# Boost.net
KiCad netlist of a schematic drawn in Altium Designer
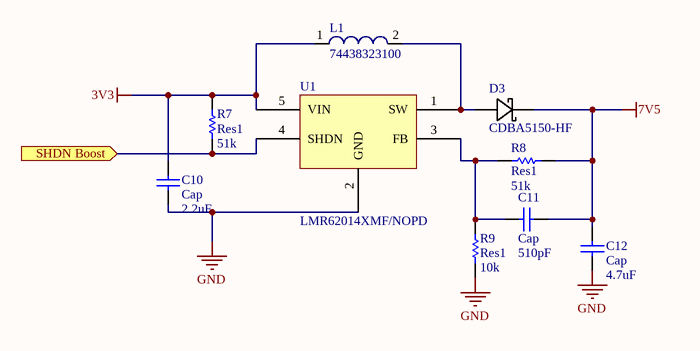
[diagram p0: Boost.SchDoc]

(export (version "E")
  (design (tool "Eeschema 10.0.6"))
  (components
    (comp (ref "C10")
      (value "Cap")
      (footprint "1608[0603]")
      (description "Capacitor")
      (fields (field (name "ALTIUM_VALUE") "2.2uF") (field (name "PUBLISHER") "Altium Limited"))
      (libsource (lib "Miscellaneous Devices") (part "Cap"))
    )
    (comp (ref "C11")
      (value "Cap")
      (footprint "6-0805_M")
      (description "Capacitor")
      (fields (field (name "ALTIUM_VALUE") "510pF") (field (name "PUBLISHER") "Altium Limited"))
      (libsource (lib "Miscellaneous Devices") (part "Cap"))
    )
    (comp (ref "C12")
      (value "Cap")
      (footprint "6-0805_M")
      (description "Capacitor")
      (fields (field (name "ALTIUM_VALUE") "4.7uF") (field (name "PUBLISHER") "Altium Limited"))
      (libsource (lib "Miscellaneous Devices") (part "Cap"))
    )
    (comp (ref "D3")
      (value "CDBA5150-HF")
      (footprint "CDBA5")
      (description "No Description Available")
      (fields (field (name "COPYRIGHT") "Copyright (C) 2018 Accelerated Designs. All rights reserved"))
      (libsource (lib "schottlky diode 5A") (part "CDBA5150-HF"))
    )
    (comp (ref "L1")
      (value "74438323100")
      (footprint "SMD 2510")
      (description "Power Multilayer Inductor WE-MAPI, L=10.0µH")
      (fields (field (name "MANUFACTURER") "Wuerth Elektronik"))
      (libsource (lib "Altium Content Vault") (part "WE-IND-INDUCTOR-2"))
    )
    (comp (ref "R7")
      (value "Res1")
      (footprint "1608[0603]")
      (description "Resistor")
      (fields (field (name "ALTIUM_VALUE") "51k") (field (name "PUBLISHER") "Altium Limited"))
      (libsource (lib "Miscellaneous Devices") (part "Res1"))
    )
    (comp (ref "R8")
      (value "Res1")
      (footprint "1608[0603]")
      (description "Resistor")
      (fields (field (name "ALTIUM_VALUE") "51k") (field (name "PUBLISHER") "Altium Limited"))
      (libsource (lib "Miscellaneous Devices") (part "Res1"))
    )
    (comp (ref "R9")
      (value "Res1")
      (footprint "0402-A")
      (description "Resistor")
      (fields (field (name "ALTIUM_VALUE") "10k") (field (name "PUBLISHER") "Altium Limited"))
      (libsource (lib "Miscellaneous Devices") (part "Res1"))
    )
    (comp (ref "U1")
      (value "LMR62014XMF/NOPD")
      (footprint "SOT95P280X145-5N")
      (libsource (lib "BPDC Library") (part "LMR62014XMF/NOPD"))
    )
  )
  (nets
    (net (code "1") (name "/SHDN Boost") (class "Default")
      (node (ref "R7") (pin "2") (pinfunction "2_2") (pintype "passive"))
      (node (ref "U1") (pin "4") (pinfunction "SHDN_4") (pintype "passive"))
    )
    (net (code "2") (name "3V3") (class "Default")
      (node (ref "C10") (pin "2") (pinfunction "2_2") (pintype "passive"))
      (node (ref "L1") (pin "1") (pinfunction "1_1") (pintype "passive"))
      (node (ref "R7") (pin "1") (pinfunction "1_1") (pintype "passive"))
      (node (ref "U1") (pin "5") (pinfunction "VIN_5") (pintype "passive"))
    )
    (net (code "3") (name "7V5") (class "Default")
      (node (ref "C11") (pin "1") (pinfunction "1_1") (pintype "passive"))
      (node (ref "C12") (pin "2") (pinfunction "2_2") (pintype "passive"))
      (node (ref "D3") (pin "1") (pinfunction "1_1") (pintype "passive"))
      (node (ref "R8") (pin "2") (pinfunction "2_2") (pintype "passive"))
    )
    (net (code "4") (name "GND") (class "Default")
      (node (ref "C10") (pin "1") (pinfunction "1_1") (pintype "passive"))
      (node (ref "C12") (pin "1") (pinfunction "1_1") (pintype "passive"))
      (node (ref "R9") (pin "2") (pinfunction "2_2") (pintype "passive"))
      (node (ref "U1") (pin "2") (pinfunction "GND_2") (pintype "passive"))
    )
    (net (code "5") (name "Net-(U1-FB)") (class "Default")
      (node (ref "C11") (pin "2") (pinfunction "2_2") (pintype "passive"))
      (node (ref "R8") (pin "1") (pinfunction "1_1") (pintype "passive"))
      (node (ref "R9") (pin "1") (pinfunction "1_1") (pintype "passive"))
      (node (ref "U1") (pin "3") (pinfunction "FB_3") (pintype "passive"))
    )
    (net (code "6") (name "Net-(U1-SW)") (class "Default")
      (node (ref "D3") (pin "2") (pinfunction "2_2") (pintype "passive"))
      (node (ref "L1") (pin "2") (pinfunction "2_2") (pintype "passive"))
      (node (ref "U1") (pin "1") (pinfunction "SW_1") (pintype "passive"))
    )
  )
)
